# play.net
KiCad netlist of a schematic drawn in EAGLE
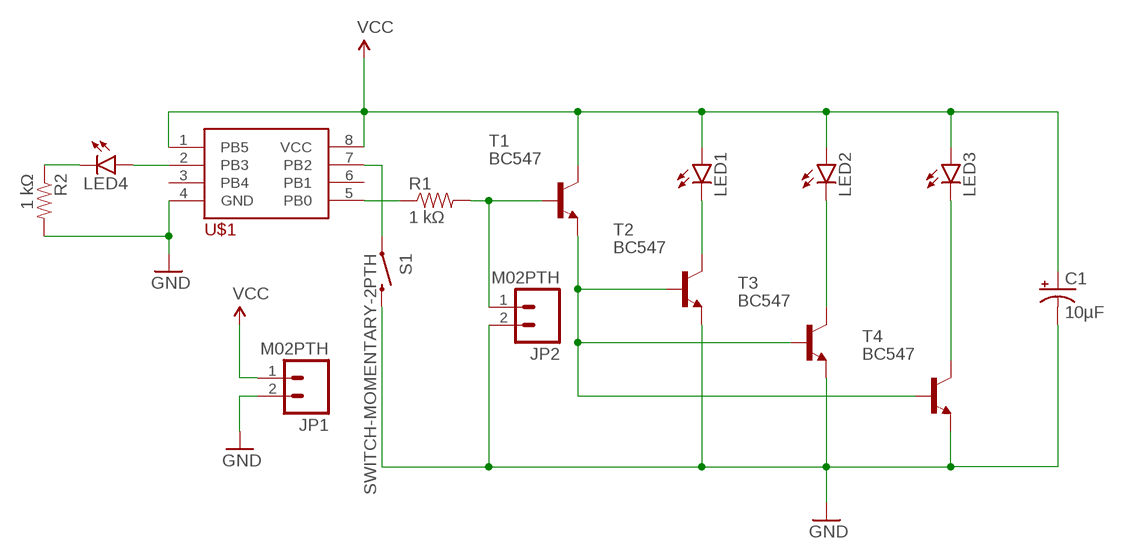
[diagram p0: schematic, sheet 1]

(export (version "E")
  (design (tool "Eeschema 10.0.6"))
  (components
    (comp (ref "C1")
      (value "10µF")
      (footprint "eagle-import:CPOL-RADIAL-10UF-25V")
      (libsource (lib "eagle-import") (part "CAP_POLPTH2"))
    )
    (comp (ref "JP1")
      (value "M02PTH")
      (footprint "eagle-import:1X02")
      (libsource (lib "eagle-import") (part "M02PTH"))
    )
    (comp (ref "JP2")
      (value "M02PTH")
      (footprint "eagle-import:1X02")
      (libsource (lib "eagle-import") (part "M02PTH"))
    )
    (comp (ref "LED1")
      (value "LED5MM")
      (footprint "eagle-import:LED5MM")
      (libsource (lib "eagle-import") (part "LED5MM"))
    )
    (comp (ref "LED2")
      (value "LED5MM")
      (footprint "eagle-import:LED5MM")
      (libsource (lib "eagle-import") (part "LED5MM"))
    )
    (comp (ref "LED3")
      (value "LED5MM")
      (footprint "eagle-import:LED5MM")
      (libsource (lib "eagle-import") (part "LED5MM"))
    )
    (comp (ref "LED4")
      (value "LED3MM")
      (footprint "eagle-import:LED3MM")
      (libsource (lib "eagle-import") (part "LED3MM"))
    )
    (comp (ref "R1")
      (value "1 kΩ")
      (footprint "eagle-import:AXIAL-0.4")
      (libsource (lib "eagle-import") (part "SparkFun-Resistors_RESISTORPTH-1/4W"))
    )
    (comp (ref "R2")
      (value "1 kΩ")
      (footprint "eagle-import:AXIAL-0.4")
      (libsource (lib "eagle-import") (part "RESISTORPTH-1/4W"))
    )
    (comp (ref "S1")
      (value "SWITCH-MOMENTARY-2PTH")
      (footprint "eagle-import:TACTILE-PTH")
      (libsource (lib "eagle-import") (part "SWITCH-MOMENTARY-2PTH"))
    )
    (comp (ref "T1")
      (value "BC547")
      (footprint "eagle-import:TO92")
      (libsource (lib "eagle-import") (part "transistor-neu-to92_BC547"))
    )
    (comp (ref "T2")
      (value "BC547")
      (footprint "eagle-import:TO92")
      (libsource (lib "eagle-import") (part "transistor-neu-to92_BC547"))
    )
    (comp (ref "T3")
      (value "BC547")
      (footprint "eagle-import:TO92")
      (libsource (lib "eagle-import") (part "BC547"))
    )
    (comp (ref "T4")
      (value "BC547")
      (footprint "eagle-import:TO92")
      (libsource (lib "eagle-import") (part "BC547"))
    )
    (comp (ref "U$1")
      (value "ATTINY85")
      (footprint "eagle-import:DIP8")
      (libsource (lib "eagle-import") (part "ATTINY85"))
    )
  )
  (nets
    (net (code "1") (name "GND") (class "Default")
      (node (ref "C1") (pin "2") (pinfunction "-_2") (pintype "passive"))
      (node (ref "JP1") (pin "2") (pinfunction "2_2") (pintype "passive"))
      (node (ref "JP2") (pin "2") (pinfunction "2_2") (pintype "passive"))
      (node (ref "R2") (pin "P$2") (pinfunction "2_P$2") (pintype "passive"))
      (node (ref "S1") (pin "3") (pinfunction "2_3") (pintype "passive"))
      (node (ref "T2") (pin "1") (pinfunction "E_1") (pintype "passive"))
      (node (ref "T3") (pin "1") (pinfunction "E_1") (pintype "passive"))
      (node (ref "T4") (pin "1") (pinfunction "E_1") (pintype "passive"))
      (node (ref "U$1") (pin "4") (pinfunction "GND_4") (pintype "bidirectional"))
    )
    (net (code "2") (name "Net-(LED1-C)") (class "Default")
      (node (ref "LED1") (pin "K") (pinfunction "C_K") (pintype "passive"))
      (node (ref "T2") (pin "3") (pinfunction "C_3") (pintype "passive"))
    )
    (net (code "3") (name "Net-(LED2-C)") (class "Default")
      (node (ref "LED2") (pin "K") (pinfunction "C_K") (pintype "passive"))
      (node (ref "T3") (pin "3") (pinfunction "C_3") (pintype "passive"))
    )
    (net (code "4") (name "Net-(LED3-C)") (class "Default")
      (node (ref "LED3") (pin "K") (pinfunction "C_K") (pintype "passive"))
      (node (ref "T4") (pin "3") (pinfunction "C_3") (pintype "passive"))
    )
    (net (code "5") (name "Net-(LED4-C)") (class "Default")
      (node (ref "LED4") (pin "K") (pinfunction "C_K") (pintype "passive"))
      (node (ref "R2") (pin "P$1") (pinfunction "1_P$1") (pintype "passive"))
    )
    (net (code "6") (name "Net-(R1-1)") (class "Default")
      (node (ref "R1") (pin "P$1") (pinfunction "1_P$1") (pintype "passive"))
      (node (ref "U$1") (pin "5") (pinfunction "PB0_5") (pintype "bidirectional"))
    )
    (net (code "7") (name "Net-(R1-2)") (class "Default")
      (node (ref "JP2") (pin "1") (pinfunction "1_1") (pintype "passive"))
      (node (ref "R1") (pin "P$2") (pinfunction "2_P$2") (pintype "passive"))
      (node (ref "T1") (pin "2") (pinfunction "B_2") (pintype "passive"))
    )
    (net (code "8") (name "Net-(T1-E)") (class "Default")
      (node (ref "T1") (pin "1") (pinfunction "E_1") (pintype "passive"))
      (node (ref "T2") (pin "2") (pinfunction "B_2") (pintype "passive"))
      (node (ref "T3") (pin "2") (pinfunction "B_2") (pintype "passive"))
      (node (ref "T4") (pin "2") (pinfunction "B_2") (pintype "passive"))
    )
    (net (code "9") (name "Net-(U$1-PB2)") (class "Default")
      (node (ref "S1") (pin "1") (pinfunction "1_1") (pintype "passive"))
      (node (ref "U$1") (pin "7") (pinfunction "PB2_7") (pintype "bidirectional"))
    )
    (net (code "10") (name "Net-(U$1-PB3)") (class "Default")
      (node (ref "LED4") (pin "A") (pinfunction "A_A") (pintype "passive"))
      (node (ref "U$1") (pin "2") (pinfunction "PB3_2") (pintype "bidirectional"))
    )
    (net (code "11") (name "VCC") (class "Default")
      (node (ref "C1") (pin "1") (pinfunction "+_1") (pintype "passive"))
      (node (ref "JP1") (pin "1") (pinfunction "1_1") (pintype "passive"))
      (node (ref "LED1") (pin "A") (pinfunction "A_A") (pintype "passive"))
      (node (ref "LED2") (pin "A") (pinfunction "A_A") (pintype "passive"))
      (node (ref "LED3") (pin "A") (pinfunction "A_A") (pintype "passive"))
      (node (ref "T1") (pin "3") (pinfunction "C_3") (pintype "passive"))
      (node (ref "U$1") (pin "1") (pinfunction "PB5_1") (pintype "bidirectional"))
      (node (ref "U$1") (pin "8") (pinfunction "VCC_8") (pintype "bidirectional"))
    )
    (net (code "12") (name "unconnected-(U$1-PB1-Pad6)") (class "Default")
      (node (ref "U$1") (pin "6") (pinfunction "PB1_6") (pintype "bidirectional"))
    )
    (net (code "13") (name "unconnected-(U$1-PB4-Pad3)") (class "Default")
      (node (ref "U$1") (pin "3") (pinfunction "PB4_3") (pintype "bidirectional"))
    )
  )
)
